# Motor_Control.net
KiCad netlist of a schematic drawn in Altium Designer
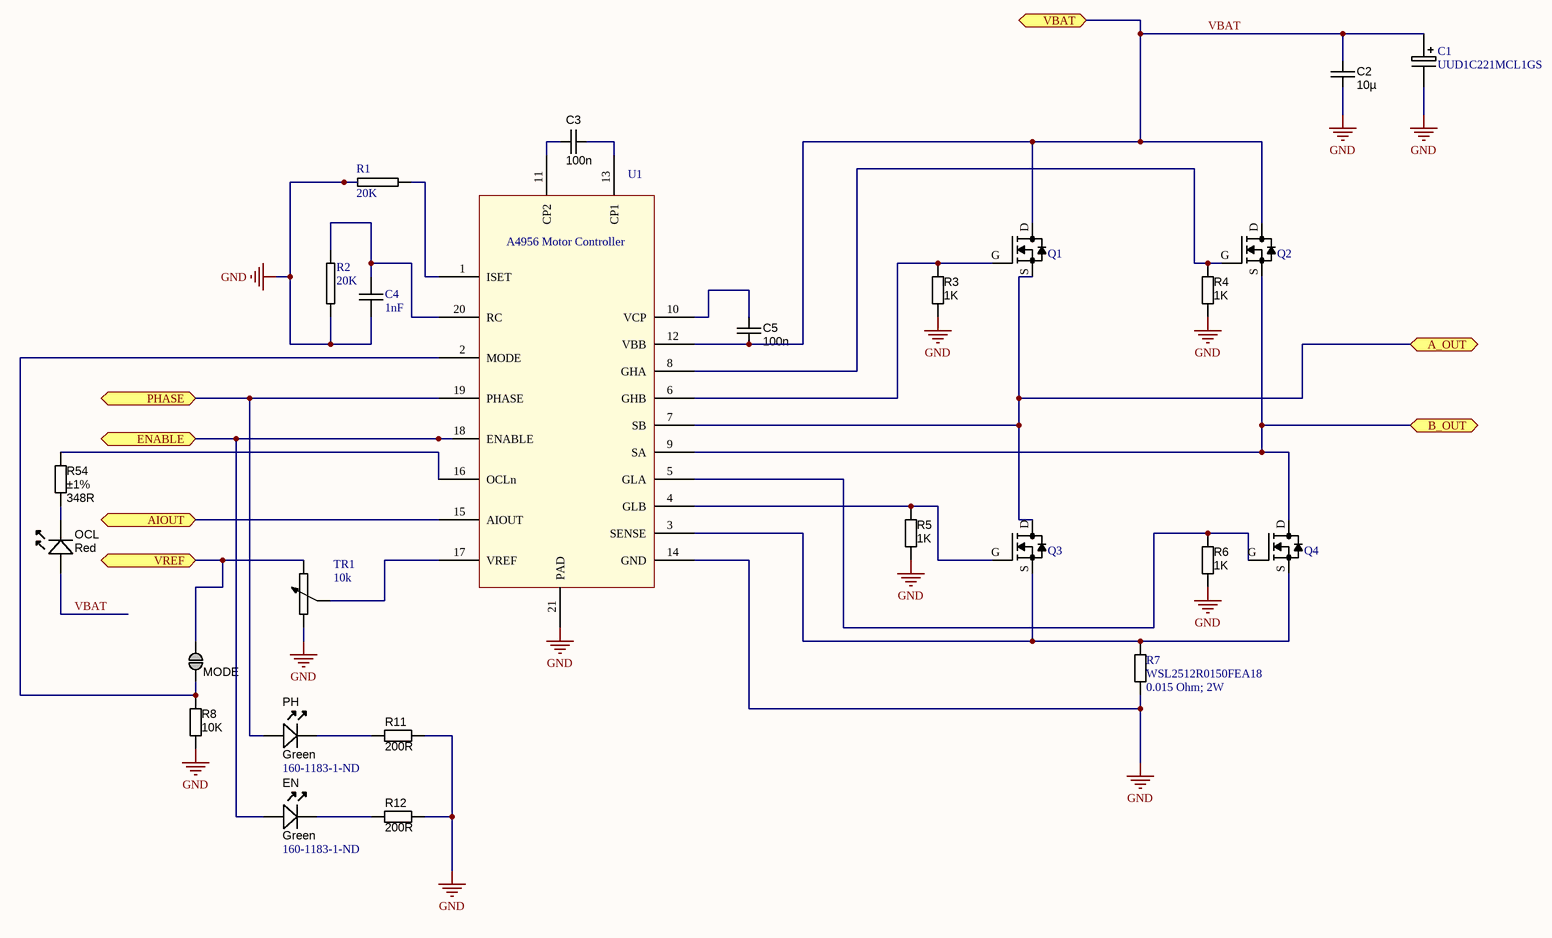
[diagram p0: Motor_Control.SchDoc]

(export (version "E")
  (design (tool "Eeschema 10.0.6"))
  (components
    (comp (ref "C1")
      (value "UUD1C221MCL1GS")
      (footprint "NICH 6.3mm 7.7mm")
      (description "GENERIC CAPACITOR POLARISED")
      (libsource (lib "SMD Capacitors Electrolytic") (part "NICHICON_220uF_16V"))
    )
    (comp (ref "C2")
      (value "10µ")
      (footprint "CAPC2012X135N")
      (description "Capacitor SMD Cer 10uF 10% 16V X7R 0805")
      (fields (field (name "TOLERANCE") "±10%") (field (name "Comment") "approved sub OK"))
      (libsource (lib "PBL - Capacitors") (part "CAPC_10u_0805_16V"))
    )
    (comp (ref "C3")
      (value "100n")
      (footprint "CAPC1608X90N")
      (description "Capacitor SMD Cer 100nF 10% 50V X7R 0603")
      (fields (field (name "TOLERANCE") "±10%") (field (name "Comment") "approved sub OK"))
      (libsource (lib "PBL - Capacitors") (part "CAPC_100n_0603_X7R_50V_10%"))
    )
    (comp (ref "C4")
      (value "1nF")
      (footprint "0603C-GENERIC")
      (description "CAPACITOR 0603 CERAMIC")
      (libsource (lib "SMD Capacitors 0603") (part "0603C-1NF-50V-X7R"))
    )
    (comp (ref "C5")
      (value "100n")
      (footprint "CAPC1608X90N")
      (description "Capacitor SMD Cer 100nF 10% 50V X7R 0603")
      (fields (field (name "TOLERANCE") "±10%") (field (name "Comment") "approved sub OK"))
      (libsource (lib "PBL - Capacitors") (part "CAPC_100n_0603_X7R_50V_10%"))
    )
    (comp (ref "EN")
      (value "Green")
      (footprint "LED-0603-GREEN")
      (description "LED 0603 SMD Green 525nm 350mcd 20mA")
      (fields (field (name "SUPPLIER PART NUMBER 1") "160-1183-1-ND"))
      (libsource (lib "PBL - Light Sources") (part "LED_SMD_Green_0603_525nm_350mcd"))
    )
    (comp (ref "MODE")
      (value "Jumper")
      (footprint "JUMP1")
      (description "SMD jumper")
      (libsource (lib "PBL - Pads and Jumpers") (part "JUMP1"))
    )
    (comp (ref "OCL")
      (value "Red")
      (footprint "LED-0603-RED")
      (description "LED 0603 SMD Hyper Red 630nm 220mcd 20mA")
      (libsource (lib "PBL - Light Sources") (part "LED_SMD_Red_0603_220mcd"))
    )
    (comp (ref "PH")
      (value "Green")
      (footprint "LED-0603-GREEN")
      (description "LED 0603 SMD Green 525nm 350mcd 20mA")
      (fields (field (name "SUPPLIER PART NUMBER 1") "160-1183-1-ND"))
      (libsource (lib "PBL - Light Sources") (part "LED_SMD_Green_0603_525nm_350mcd"))
    )
    (comp (ref "Q1")
      (value "SIS406DN")
      (footprint "1212-8 PowerPAK Single")
      (libsource (lib "PBL - Transistors") (part "MOSFET_N_CHAN_SIS406DN"))
    )
    (comp (ref "Q2")
      (value "SIS406DN")
      (footprint "1212-8 PowerPAK Single")
      (libsource (lib "PBL - Transistors") (part "MOSFET_N_CHAN_SIS406DN"))
    )
    (comp (ref "Q3")
      (value "SIS406DN")
      (footprint "1212-8 PowerPAK Single")
      (libsource (lib "PBL - Transistors") (part "MOSFET_N_CHAN_SIS406DN"))
    )
    (comp (ref "Q4")
      (value "SIS406DN")
      (footprint "1212-8 PowerPAK Single")
      (libsource (lib "PBL - Transistors") (part "MOSFET_N_CHAN_SIS406DN"))
    )
    (comp (ref "R1")
      (value "20K")
      (footprint "0603R-GENERIC")
      (description "GENERIC RESISTOR 0603")
      (fields
        (field (name "MANUFACTURER") "Stackpole Electronics Inc")
        (field (name "MANUFACTURER PART NUMBER") "RNCF 16 T2 20K .1% R")
      )
      (libsource (lib "SMD Resistors 0603") (part "0603R-20K"))
    )
    (comp (ref "R2")
      (value "20K")
      (footprint "0603R-GENERIC")
      (description "GENERIC RESISTOR 0603")
      (fields
        (field (name "MANUFACTURER") "Stackpole Electronics Inc")
        (field (name "MANUFACTURER PART NUMBER") "RNCF 16 T2 20K .1% R")
      )
      (libsource (lib "SMD Resistors 0603") (part "0603R-20K"))
    )
    (comp (ref "R3")
      (value "1K")
      (footprint "RESC1608X55N")
      (description "Resistor SMD chip 1k Ohm 0.1W 5% 0603")
      (fields (field (name "TOLERANCE") "±5%") (field (name "Comment") "Thick Film"))
      (libsource (lib "PBL - Resistors") (part "RES_1K_0603_5%"))
    )
    (comp (ref "R4")
      (value "1K")
      (footprint "RESC1608X55N")
      (description "Resistor SMD chip 1k Ohm 0.1W 5% 0603")
      (fields (field (name "TOLERANCE") "±5%") (field (name "Comment") "Thick Film"))
      (libsource (lib "PBL - Resistors") (part "RES_1K_0603_5%"))
    )
    (comp (ref "R5")
      (value "1K")
      (footprint "RESC1608X55N")
      (description "Resistor SMD chip 1k Ohm 0.1W 5% 0603")
      (fields (field (name "TOLERANCE") "±5%") (field (name "Comment") "Thick Film"))
      (libsource (lib "PBL - Resistors") (part "RES_1K_0603_5%"))
    )
    (comp (ref "R6")
      (value "1K")
      (footprint "RESC1608X55N")
      (description "Resistor SMD chip 1k Ohm 0.1W 5% 0603")
      (fields (field (name "TOLERANCE") "±5%") (field (name "Comment") "Thick Film"))
      (libsource (lib "PBL - Resistors") (part "RES_1K_0603_5%"))
    )
    (comp (ref "R7")
      (value "WSL2512R0150FEA18")
      (footprint "RESC_2512")
      (description "RES SMD 0.015 OHM 1% 2W 2512")
      (fields (field (name "RATING") "0.015 Ohm; 2W"))
      (libsource (lib "RyanMasterLib") (part "RES_0.015"))
    )
    (comp (ref "R8")
      (value "10K")
      (footprint "RESC1608X55N")
      (description "Resistor SMD chip 10k Ohm 0.1W 5% 0603")
      (fields (field (name "TOLERANCE") "±5%") (field (name "Comment") "Thick Film"))
      (libsource (lib "PBL - Resistors") (part "RES_10K_0603_5%"))
    )
    (comp (ref "R11")
      (value "200R")
      (footprint "RESC1608X55N")
      (description "Resistor SMD chip 200 Ohm 0.1W 5% 0603")
      (fields (field (name "TOLERANCE") "±5%") (field (name "Comment") "Thick Film"))
      (libsource (lib "PBL - Resistors") (part "RES_200R_0603_5%"))
    )
    (comp (ref "R12")
      (value "200R")
      (footprint "RESC1608X55N")
      (description "Resistor SMD chip 200 Ohm 0.1W 5% 0603")
      (fields (field (name "TOLERANCE") "±5%") (field (name "Comment") "Thick Film"))
      (libsource (lib "PBL - Resistors") (part "RES_200R_0603_5%"))
    )
    (comp (ref "R54")
      (value "348R")
      (footprint "RESC1608X55N")
      (description "Resistor SMD chip 348 Ohm 0.1W 1% 0603")
      (fields (field (name "TOLERANCE") "±1%") (field (name "Comment") "Thin Film"))
      (libsource (lib "PBL - Resistors") (part "RES_348R_0603_1%"))
    )
    (comp (ref "TR1")
      (value "10k")
      (footprint "TRIM3224")
      (description "GENERIC SMD TRIMMER")
      (fields (field (name "TOLERANCE") "±10%") (field (name "MANUFACTURER PART NUMBER") "3224X-1-103E"))
      (libsource (lib "SMD Resistors") (part "R-TRIM-SMD-10k"))
    )
    (comp (ref "U1")
      (value "A4956")
      (footprint "QFN-20 - 8mil Pad Spacing")
      (description "PWM Motor Controller")
      (libsource (lib "PBL - Integrated Circuits") (part "Motor_CTRL_IC_A4956"))
    )
  )
  (nets
    (net (code "1") (name "/AIOUT") (class "Default")
      (node (ref "U1") (pin "15") (pinfunction "AIOUT_15") (pintype "passive"))
    )
    (net (code "2") (name "/A_OUT") (class "Default")
      (node (ref "Q1") (pin "S") (pintype "passive"))
      (node (ref "Q3") (pin "D") (pintype "passive"))
      (node (ref "U1") (pin "7") (pinfunction "SB_7") (pintype "passive"))
    )
    (net (code "3") (name "/B_OUT") (class "Default")
      (node (ref "Q2") (pin "S") (pintype "passive"))
      (node (ref "Q4") (pin "D") (pintype "passive"))
      (node (ref "U1") (pin "9") (pinfunction "SA_9") (pintype "passive"))
    )
    (net (code "4") (name "/ENABLE") (class "Default")
      (node (ref "EN") (pin "A") (pinfunction "A_A") (pintype "passive"))
      (node (ref "U1") (pin "18") (pinfunction "ENABLE_18") (pintype "passive"))
    )
    (net (code "5") (name "/PHASE") (class "Default")
      (node (ref "PH") (pin "A") (pinfunction "A_A") (pintype "passive"))
      (node (ref "U1") (pin "19") (pinfunction "PHASE_19") (pintype "passive"))
    )
    (net (code "6") (name "/VBAT") (class "Default")
      (node (ref "C1") (pin "+") (pinfunction "+_+") (pintype "passive"))
      (node (ref "C2") (pin "1") (pintype "passive"))
      (node (ref "C5") (pin "2") (pintype "passive"))
      (node (ref "OCL") (pin "A") (pinfunction "A_A") (pintype "passive"))
      (node (ref "Q1") (pin "D") (pintype "passive"))
      (node (ref "Q2") (pin "D") (pintype "passive"))
      (node (ref "U1") (pin "12") (pinfunction "VBB_12") (pintype "passive"))
    )
    (net (code "7") (name "/VREF") (class "Default")
      (node (ref "MODE") (pin "2") (pintype "passive"))
      (node (ref "TR1") (pin "2") (pinfunction "2_2") (pintype "passive"))
    )
    (net (code "8") (name "GND") (class "Default")
      (node (ref "C1") (pin "-") (pinfunction "-_-") (pintype "passive"))
      (node (ref "C2") (pin "2") (pintype "passive"))
      (node (ref "C4") (pin "2") (pintype "passive"))
      (node (ref "R1") (pin "1") (pintype "passive"))
      (node (ref "R11") (pin "2") (pinfunction "2_2") (pintype "passive"))
      (node (ref "R12") (pin "2") (pinfunction "2_2") (pintype "passive"))
      (node (ref "R2") (pin "2") (pintype "passive"))
      (node (ref "R3") (pin "2") (pinfunction "2_2") (pintype "passive"))
      (node (ref "R4") (pin "2") (pinfunction "2_2") (pintype "passive"))
      (node (ref "R5") (pin "2") (pinfunction "2_2") (pintype "passive"))
      (node (ref "R6") (pin "2") (pinfunction "2_2") (pintype "passive"))
      (node (ref "R7") (pin "2") (pinfunction "2_2") (pintype "passive"))
      (node (ref "R8") (pin "2") (pinfunction "2_2") (pintype "passive"))
      (node (ref "TR1") (pin "1") (pinfunction "1_1") (pintype "passive"))
      (node (ref "U1") (pin "14") (pinfunction "GND_14") (pintype "passive"))
      (node (ref "U1") (pin "21") (pinfunction "PAD_21") (pintype "passive"))
    )
    (net (code "9") (name "Net-(EN-PadK)") (class "Default")
      (node (ref "EN") (pin "K") (pinfunction "K_K") (pintype "passive"))
      (node (ref "R12") (pin "1") (pinfunction "1_1") (pintype "passive"))
    )
    (net (code "10") (name "Net-(OCL-PadK)") (class "Default")
      (node (ref "OCL") (pin "K") (pinfunction "K_K") (pintype "passive"))
      (node (ref "R54") (pin "2") (pinfunction "2_2") (pintype "passive"))
    )
    (net (code "11") (name "Net-(PH-PadK)") (class "Default")
      (node (ref "PH") (pin "K") (pinfunction "K_K") (pintype "passive"))
      (node (ref "R11") (pin "1") (pinfunction "1_1") (pintype "passive"))
    )
    (net (code "12") (name "Net-(U1-CP1)") (class "Default")
      (node (ref "C3") (pin "2") (pintype "passive"))
      (node (ref "U1") (pin "13") (pinfunction "CP1_13") (pintype "passive"))
    )
    (net (code "13") (name "Net-(U1-CP2)") (class "Default")
      (node (ref "C3") (pin "1") (pintype "passive"))
      (node (ref "U1") (pin "11") (pinfunction "CP2_11") (pintype "passive"))
    )
    (net (code "14") (name "Net-(U1-GHA)") (class "Default")
      (node (ref "Q2") (pin "G") (pintype "passive"))
      (node (ref "R4") (pin "1") (pinfunction "1_1") (pintype "passive"))
      (node (ref "U1") (pin "8") (pinfunction "GHA_8") (pintype "passive"))
    )
    (net (code "15") (name "Net-(U1-GHB)") (class "Default")
      (node (ref "Q1") (pin "G") (pintype "passive"))
      (node (ref "R3") (pin "1") (pinfunction "1_1") (pintype "passive"))
      (node (ref "U1") (pin "6") (pinfunction "GHB_6") (pintype "passive"))
    )
    (net (code "16") (name "Net-(U1-GLA)") (class "Default")
      (node (ref "Q4") (pin "G") (pintype "passive"))
      (node (ref "R6") (pin "1") (pinfunction "1_1") (pintype "passive"))
      (node (ref "U1") (pin "5") (pinfunction "GLA_5") (pintype "passive"))
    )
    (net (code "17") (name "Net-(U1-GLB)") (class "Default")
      (node (ref "Q3") (pin "G") (pintype "passive"))
      (node (ref "R5") (pin "1") (pinfunction "1_1") (pintype "passive"))
      (node (ref "U1") (pin "4") (pinfunction "GLB_4") (pintype "passive"))
    )
    (net (code "18") (name "Net-(U1-ISET)") (class "Default")
      (node (ref "R1") (pin "2") (pintype "passive"))
      (node (ref "U1") (pin "1") (pinfunction "ISET_1") (pintype "passive"))
    )
    (net (code "19") (name "Net-(U1-MODE)") (class "Default")
      (node (ref "MODE") (pin "1") (pintype "passive"))
      (node (ref "R8") (pin "1") (pinfunction "1_1") (pintype "passive"))
      (node (ref "U1") (pin "2") (pinfunction "MODE_2") (pintype "passive"))
    )
    (net (code "20") (name "Net-(U1-OCLn)") (class "Default")
      (node (ref "R54") (pin "1") (pinfunction "1_1") (pintype "passive"))
      (node (ref "U1") (pin "16") (pinfunction "OCLn_16") (pintype "passive"))
    )
    (net (code "21") (name "Net-(U1-RC)") (class "Default")
      (node (ref "C4") (pin "1") (pintype "passive"))
      (node (ref "R2") (pin "1") (pintype "passive"))
      (node (ref "U1") (pin "20") (pinfunction "RC_20") (pintype "passive"))
    )
    (net (code "22") (name "Net-(U1-SENSE)") (class "Default")
      (node (ref "Q3") (pin "S") (pintype "passive"))
      (node (ref "Q4") (pin "S") (pintype "passive"))
      (node (ref "R7") (pin "1") (pinfunction "1_1") (pintype "passive"))
      (node (ref "U1") (pin "3") (pinfunction "SENSE_3") (pintype "passive"))
    )
    (net (code "23") (name "Net-(U1-VCP)") (class "Default")
      (node (ref "C5") (pin "1") (pintype "passive"))
      (node (ref "U1") (pin "10") (pinfunction "VCP_10") (pintype "passive"))
    )
    (net (code "24") (name "Net-(U1-VREF)") (class "Default")
      (node (ref "TR1") (pin "W") (pinfunction "W_W") (pintype "passive"))
      (node (ref "U1") (pin "17") (pinfunction "VREF_17") (pintype "passive"))
    )
  )
)
